# Business_Card_PCB_-_src1.net
KiCad netlist of a schematic drawn in EasyEDA
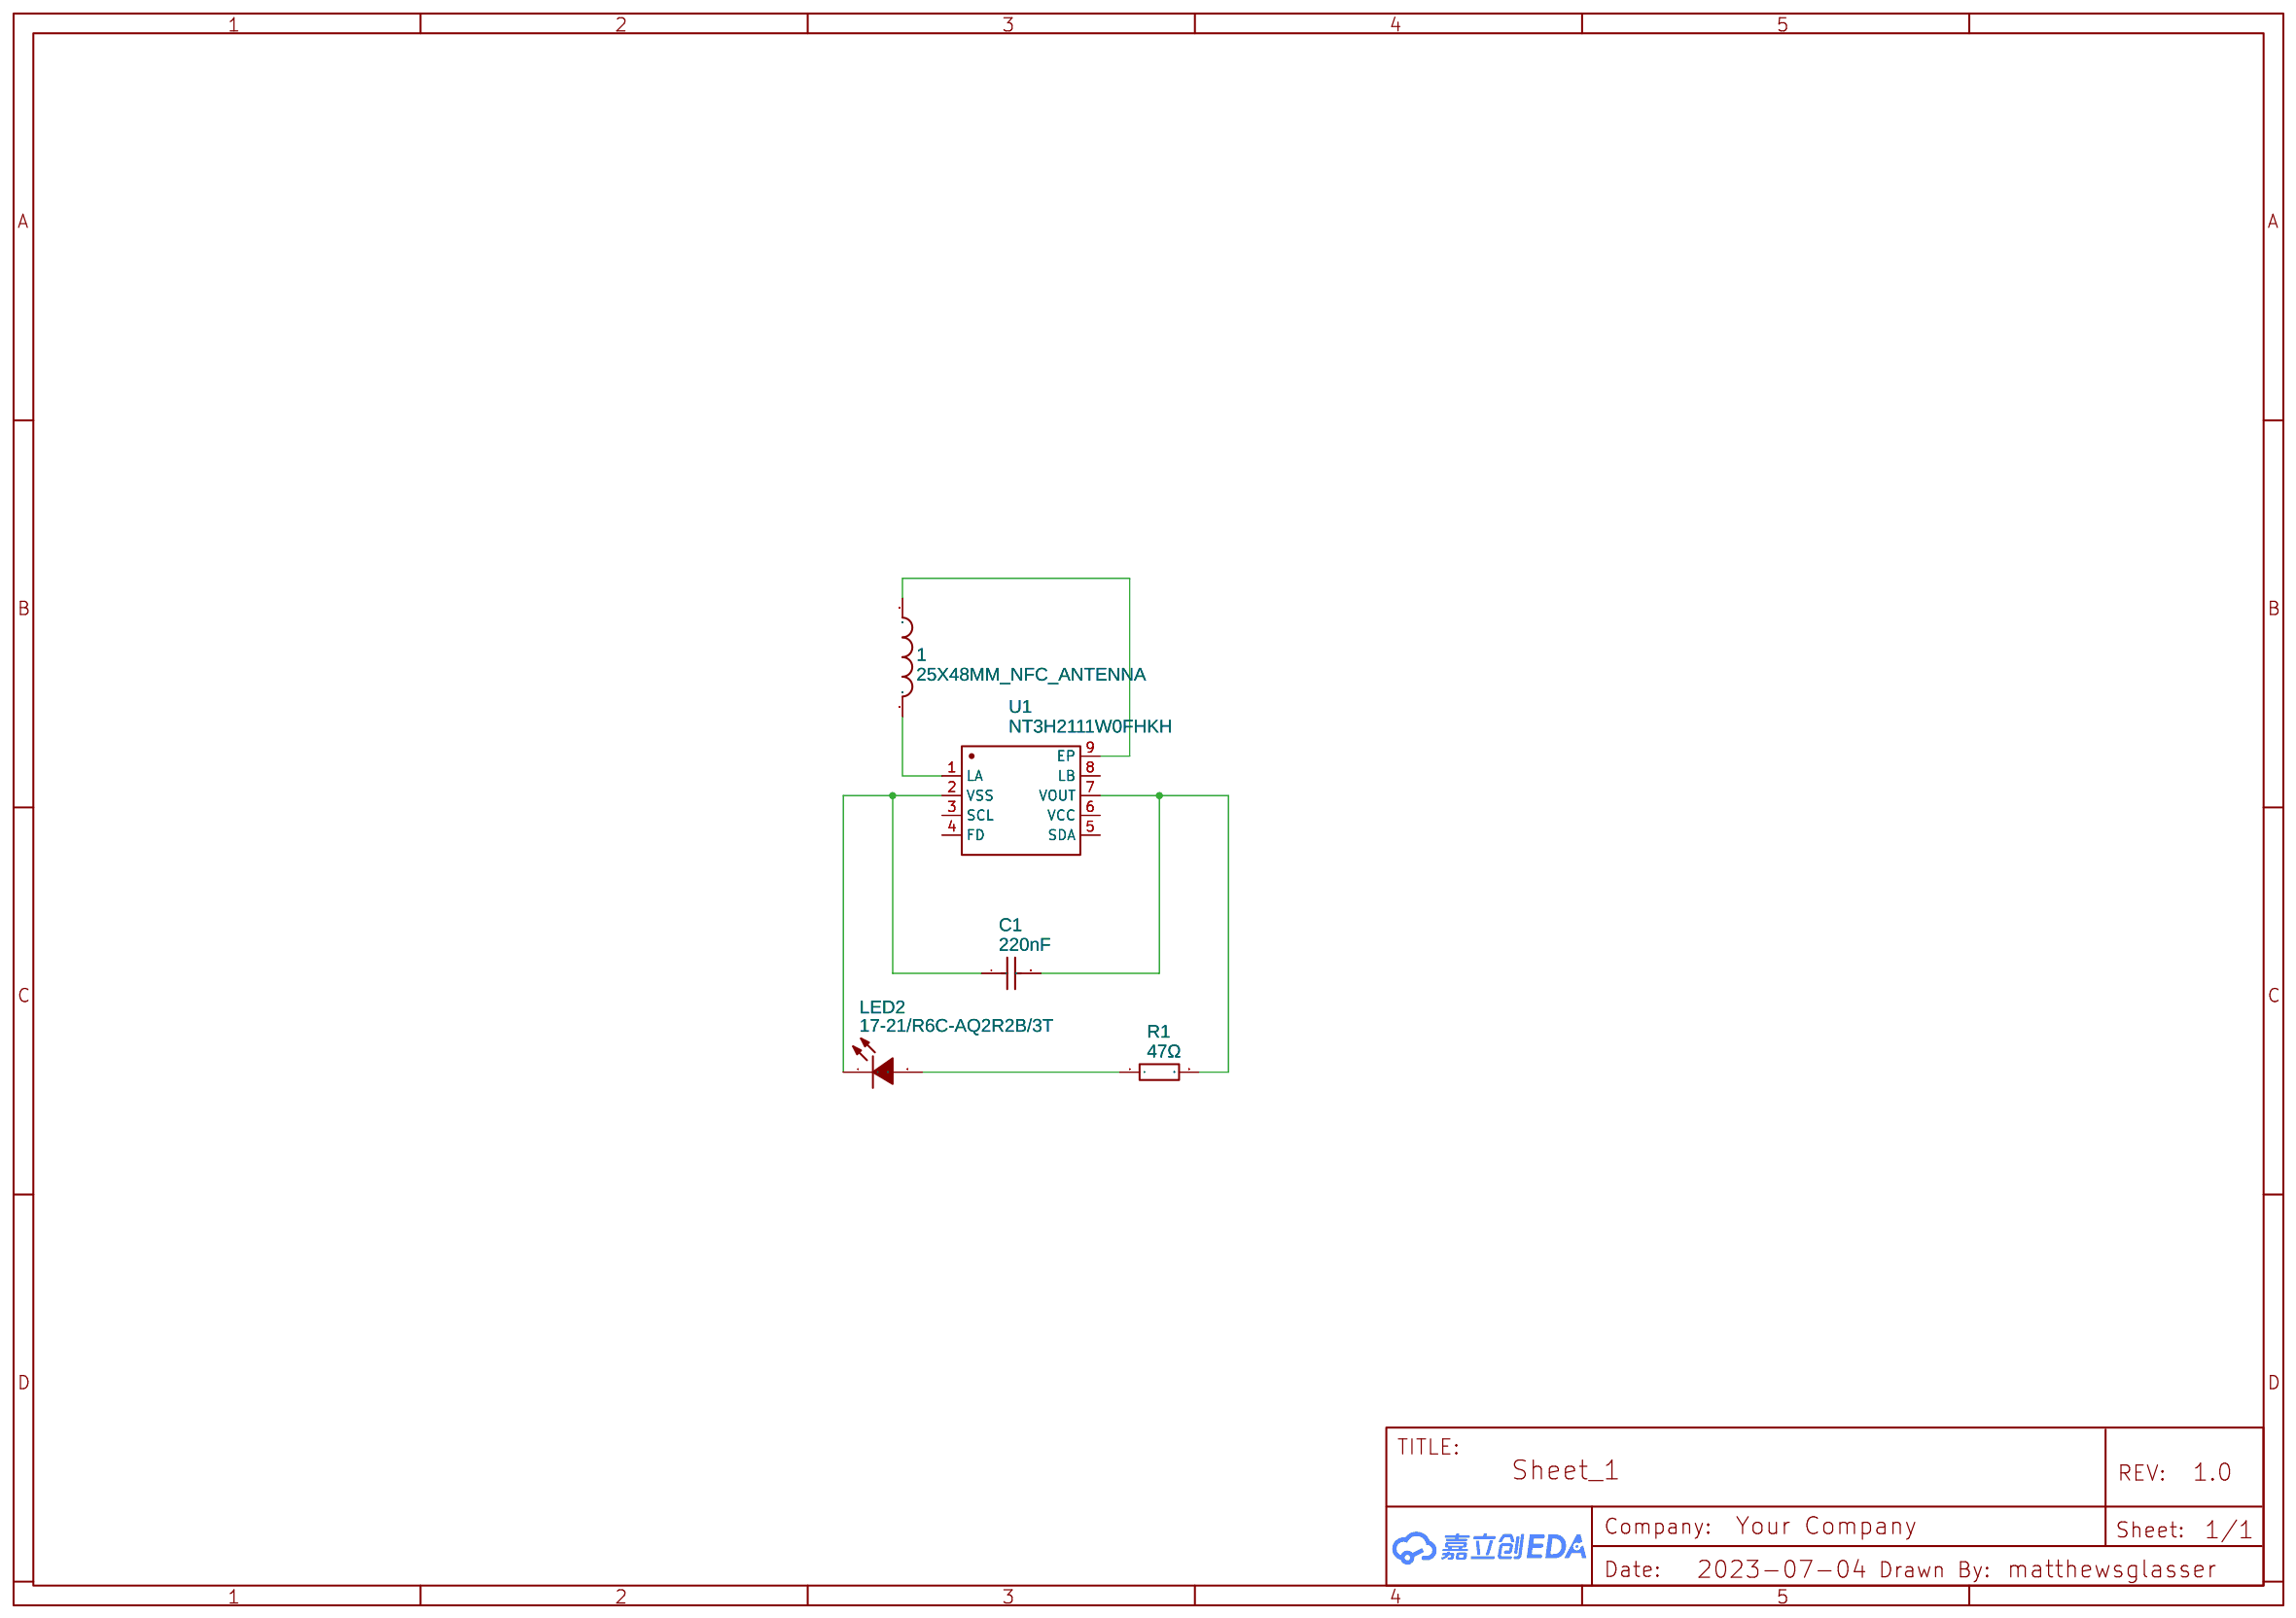
[diagram p0: schematic sheet]

(export (version "E")
  (design (tool "Eeschema 10.0.6"))
  (components
    (comp (ref "1") (value "25X48MM_NFC_ANTENNA") (libsource (lib "") (part "25X48MM_NFC_ANTENNA")))
    (comp (ref "C1")
      (value "220nF")
      (fields
        (field (name "Manufacturer Part") "CL10B224KA8NNNC")
        (field (name "Manufacturer") "SAMSUNG(三星)")
      )
      (libsource (lib "") (part "CL10B224KA8NNNC"))
    )
    (comp (ref "LED2")
      (value "17-21/R6C-AQ2R2B/3T")
      (fields (field (name "Manufacturer") "EVERLIGHT(亿光)"))
      (libsource (lib "") (part "17-21/R6C-AQ2R2B/3T"))
    )
    (comp (ref "R1")
      (value "47Ω")
      (fields
        (field (name "Manufacturer Part") "0603WAF470JT5E")
        (field (name "Manufacturer") "UNI-ROYAL(厚声)")
      )
      (libsource (lib "") (part "0603WAF470JT5E"))
    )
    (comp (ref "U1")
      (value "NT3H2111W0FHKH")
      (fields (field (name "Manufacturer") "NXP(恩智浦)"))
      (libsource (lib "") (part "NT3H2111W0FHKH"))
    )
  )
  (nets
    (net (code "1") (name "Net-(LED2-A)") (class "Default")
      (node (ref "LED2") (pin "2") (pinfunction "A_2") (pintype "unspecified"))
      (node (ref "R1") (pin "1") (pinfunction "1_1") (pintype "input"))
    )
    (net (code "2") (name "Net-(LED2-K)") (class "Default")
      (node (ref "C1") (pin "1") (pinfunction "1_1") (pintype "input"))
      (node (ref "LED2") (pin "1") (pinfunction "K_1") (pintype "unspecified"))
      (node (ref "U1") (pin "2") (pinfunction "VSS_2") (pintype "unspecified"))
    )
    (net (code "3") (name "Net-(U1-EP)") (class "Default")
      (node (ref "1") (pin "P$1") (pinfunction "P$1_P$1") (pintype "bidirectional"))
      (node (ref "U1") (pin "9") (pinfunction "EP_9") (pintype "unspecified"))
    )
    (net (code "4") (name "Net-(U1-LA)") (class "Default")
      (node (ref "1") (pin "P$2") (pinfunction "P$2_P$2") (pintype "bidirectional"))
      (node (ref "U1") (pin "1") (pinfunction "LA_1") (pintype "unspecified"))
    )
    (net (code "5") (name "Net-(U1-VOUT)") (class "Default")
      (node (ref "C1") (pin "2") (pinfunction "2_2") (pintype "input"))
      (node (ref "R1") (pin "2") (pinfunction "2_2") (pintype "input"))
      (node (ref "U1") (pin "7") (pinfunction "VOUT_7") (pintype "unspecified"))
    )
    (net (code "6") (name "unconnected-(U1-FD-Pad4)") (class "Default")
      (node (ref "U1") (pin "4") (pinfunction "FD_4") (pintype "unspecified"))
    )
    (net (code "7") (name "unconnected-(U1-LB-Pad8)") (class "Default")
      (node (ref "U1") (pin "8") (pinfunction "LB_8") (pintype "unspecified"))
    )
    (net (code "8") (name "unconnected-(U1-SCL-Pad3)") (class "Default")
      (node (ref "U1") (pin "3") (pinfunction "SCL_3") (pintype "unspecified"))
    )
    (net (code "9") (name "unconnected-(U1-SDA-Pad5)") (class "Default")
      (node (ref "U1") (pin "5") (pinfunction "SDA_5") (pintype "unspecified"))
    )
    (net (code "10") (name "unconnected-(U1-VCC-Pad6)") (class "Default")
      (node (ref "U1") (pin "6") (pinfunction "VCC_6") (pintype "unspecified"))
    )
  )
)
